# oLoRa-part-LoRa.net
KiCad netlist of a schematic drawn in EasyEDA
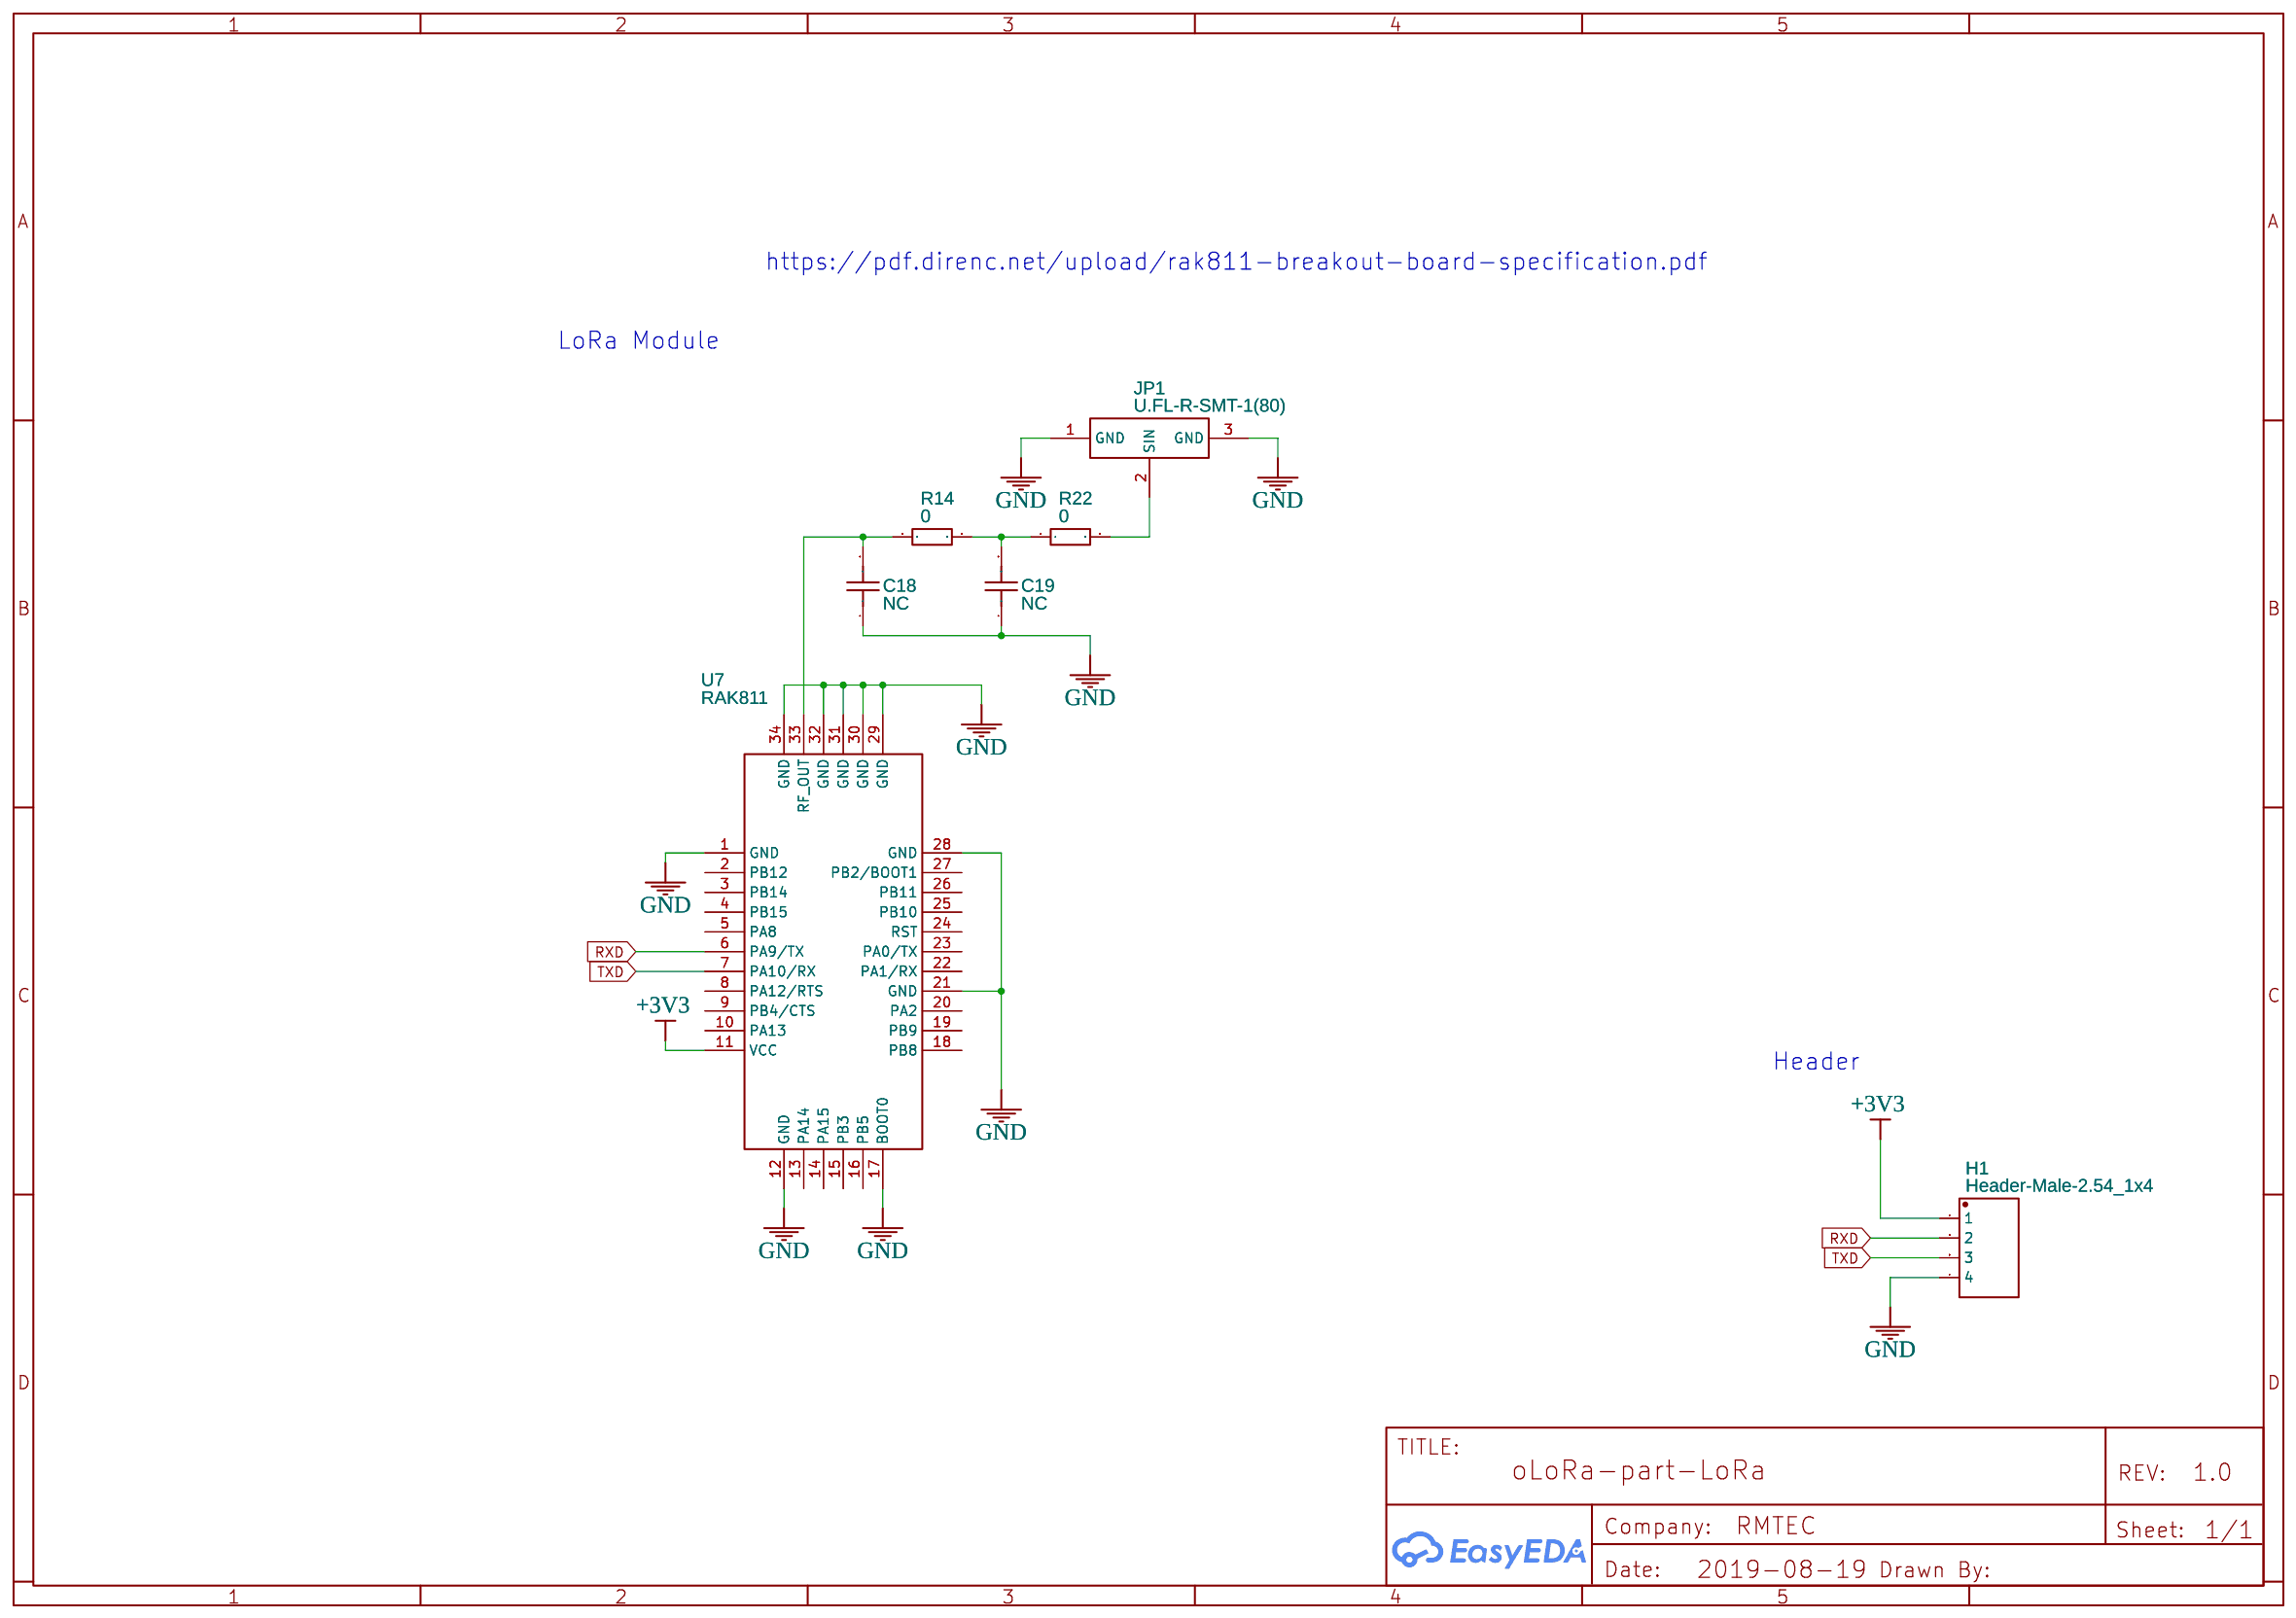
[diagram p0: schematic sheet]

(export (version "E")
  (design (tool "Eeschema 10.0.6"))
  (components
    (comp (ref "C18") (value "NC") (libsource (lib "") (part "Cap_0805_US")))
    (comp (ref "C19") (value "NC") (libsource (lib "") (part "Cap_0805_US")))
    (comp (ref "H1")
      (value "Header-Male-2.54_1x4")
      (fields
        (field (name "BOM_Manufacturer Part") "210S-1*4P L=11.6MMGold-plated black")
        (field (name "BOM_Supplier Part") "C124378")
      )
      (libsource (lib "") (part "Unknown_995_625"))
    )
    (comp (ref "JP1")
      (value "U.FL-R-SMT-1(80)")
      (fields (field (name "BOM_Supplier Part") "C88374"))
      (libsource (lib "") (part "Unknown_575_225"))
    )
    (comp (ref "R14")
      (value "0")
      (fields
        (field (name "BOM_Manufacturer Part") "0603WAF0000T5E")
        (field (name "BOM_Supplier Part") "C21189")
      )
      (libsource (lib "") (part "0603WAF0000T5E"))
    )
    (comp (ref "R22")
      (value "0")
      (fields
        (field (name "BOM_Manufacturer Part") "0603WAF0000T5E")
        (field (name "BOM_Supplier Part") "C21189")
      )
      (libsource (lib "") (part "0603WAF0000T5E"))
    )
    (comp (ref "U7") (value "RAK811") (libsource (lib "") (part "Unknown_410_475")))
  )
  (nets
    (net (code "1") (name "+3V3") (class "Default")
      (node (ref "H1") (pin "1") (pinfunction "1_1") (pintype "unspecified"))
      (node (ref "U7") (pin "11") (pinfunction "VCC_11") (pintype "unspecified"))
    )
    (net (code "2") (name "GND") (class "Default")
      (node (ref "C18") (pin "1") (pinfunction "1_1") (pintype "unspecified"))
      (node (ref "C19") (pin "1") (pinfunction "1_1") (pintype "unspecified"))
      (node (ref "H1") (pin "4") (pinfunction "4_4") (pintype "unspecified"))
      (node (ref "JP1") (pin "1") (pinfunction "GND_1") (pintype "unspecified"))
      (node (ref "JP1") (pin "3") (pinfunction "GND_3") (pintype "unspecified"))
      (node (ref "U7") (pin "1") (pinfunction "GND_1") (pintype "unspecified"))
      (node (ref "U7") (pin "12") (pinfunction "GND_12") (pintype "unspecified"))
      (node (ref "U7") (pin "17") (pinfunction "BOOT0_17") (pintype "unspecified"))
      (node (ref "U7") (pin "21") (pinfunction "GND_21") (pintype "unspecified"))
      (node (ref "U7") (pin "28") (pinfunction "GND_28") (pintype "unspecified"))
      (node (ref "U7") (pin "29") (pinfunction "GND_29") (pintype "unspecified"))
      (node (ref "U7") (pin "30") (pinfunction "GND_30") (pintype "unspecified"))
      (node (ref "U7") (pin "31") (pinfunction "GND_31") (pintype "unspecified"))
      (node (ref "U7") (pin "32") (pinfunction "GND_32") (pintype "unspecified"))
      (node (ref "U7") (pin "34") (pinfunction "GND_34") (pintype "unspecified"))
    )
    (net (code "3") (name "Net-(C19-Pad2)") (class "Default")
      (node (ref "C19") (pin "2") (pinfunction "2_2") (pintype "unspecified"))
      (node (ref "R14") (pin "2") (pinfunction "2_2") (pintype "input"))
      (node (ref "R22") (pin "1") (pinfunction "1_1") (pintype "input"))
    )
    (net (code "4") (name "Net-(JP1-SIN)") (class "Default")
      (node (ref "JP1") (pin "2") (pinfunction "SIN_2") (pintype "unspecified"))
      (node (ref "R22") (pin "2") (pinfunction "2_2") (pintype "input"))
    )
    (net (code "5") (name "Net-(U7-RF_OUT)") (class "Default")
      (node (ref "C18") (pin "2") (pinfunction "2_2") (pintype "unspecified"))
      (node (ref "R14") (pin "1") (pinfunction "1_1") (pintype "input"))
      (node (ref "U7") (pin "33") (pinfunction "RF_OUT_33") (pintype "unspecified"))
    )
    (net (code "6") (name "RXD") (class "Default")
      (node (ref "H1") (pin "2") (pinfunction "2_2") (pintype "unspecified"))
      (node (ref "U7") (pin "6") (pinfunction "PA9/TX_6") (pintype "unspecified"))
    )
    (net (code "7") (name "TXD") (class "Default")
      (node (ref "H1") (pin "3") (pinfunction "3_3") (pintype "unspecified"))
      (node (ref "U7") (pin "7") (pinfunction "PA10/RX_7") (pintype "unspecified"))
    )
    (net (code "8") (name "unconnected-(U7-PA0{slash}TX-Pad23)") (class "Default")
      (node (ref "U7") (pin "23") (pinfunction "PA0/TX_23") (pintype "unspecified"))
    )
    (net (code "9") (name "unconnected-(U7-PA1{slash}RX-Pad22)") (class "Default")
      (node (ref "U7") (pin "22") (pinfunction "PA1/RX_22") (pintype "unspecified"))
    )
    (net (code "10") (name "unconnected-(U7-PA2-Pad20)") (class "Default")
      (node (ref "U7") (pin "20") (pinfunction "PA2_20") (pintype "unspecified"))
    )
    (net (code "11") (name "unconnected-(U7-PA8-Pad5)") (class "Default")
      (node (ref "U7") (pin "5") (pinfunction "PA8_5") (pintype "unspecified"))
    )
    (net (code "12") (name "unconnected-(U7-PA12{slash}RTS-Pad8)") (class "Default")
      (node (ref "U7") (pin "8") (pinfunction "PA12/RTS_8") (pintype "unspecified"))
    )
    (net (code "13") (name "unconnected-(U7-PA13-Pad10)") (class "Default")
      (node (ref "U7") (pin "10") (pinfunction "PA13_10") (pintype "unspecified"))
    )
    (net (code "14") (name "unconnected-(U7-PA14-Pad13)") (class "Default")
      (node (ref "U7") (pin "13") (pinfunction "PA14_13") (pintype "unspecified"))
    )
    (net (code "15") (name "unconnected-(U7-PA15-Pad14)") (class "Default")
      (node (ref "U7") (pin "14") (pinfunction "PA15_14") (pintype "unspecified"))
    )
    (net (code "16") (name "unconnected-(U7-PB2{slash}BOOT1-Pad27)") (class "Default")
      (node (ref "U7") (pin "27") (pinfunction "PB2/BOOT1_27") (pintype "unspecified"))
    )
    (net (code "17") (name "unconnected-(U7-PB3-Pad15)") (class "Default")
      (node (ref "U7") (pin "15") (pinfunction "PB3_15") (pintype "unspecified"))
    )
    (net (code "18") (name "unconnected-(U7-PB4{slash}CTS-Pad9)") (class "Default")
      (node (ref "U7") (pin "9") (pinfunction "PB4/CTS_9") (pintype "unspecified"))
    )
    (net (code "19") (name "unconnected-(U7-PB5-Pad16)") (class "Default")
      (node (ref "U7") (pin "16") (pinfunction "PB5_16") (pintype "unspecified"))
    )
    (net (code "20") (name "unconnected-(U7-PB8-Pad18)") (class "Default")
      (node (ref "U7") (pin "18") (pinfunction "PB8_18") (pintype "unspecified"))
    )
    (net (code "21") (name "unconnected-(U7-PB9-Pad19)") (class "Default")
      (node (ref "U7") (pin "19") (pinfunction "PB9_19") (pintype "unspecified"))
    )
    (net (code "22") (name "unconnected-(U7-PB10-Pad25)") (class "Default")
      (node (ref "U7") (pin "25") (pinfunction "PB10_25") (pintype "unspecified"))
    )
    (net (code "23") (name "unconnected-(U7-PB11-Pad26)") (class "Default")
      (node (ref "U7") (pin "26") (pinfunction "PB11_26") (pintype "unspecified"))
    )
    (net (code "24") (name "unconnected-(U7-PB12-Pad2)") (class "Default")
      (node (ref "U7") (pin "2") (pinfunction "PB12_2") (pintype "unspecified"))
    )
    (net (code "25") (name "unconnected-(U7-PB14-Pad3)") (class "Default")
      (node (ref "U7") (pin "3") (pinfunction "PB14_3") (pintype "unspecified"))
    )
    (net (code "26") (name "unconnected-(U7-PB15-Pad4)") (class "Default")
      (node (ref "U7") (pin "4") (pinfunction "PB15_4") (pintype "unspecified"))
    )
    (net (code "27") (name "unconnected-(U7-RST-Pad24)") (class "Default")
      (node (ref "U7") (pin "24") (pinfunction "RST_24") (pintype "unspecified"))
    )
  )
)
